# CH32L103G8R6-R0.net
KiCad netlist of a schematic drawn in Altium Designer
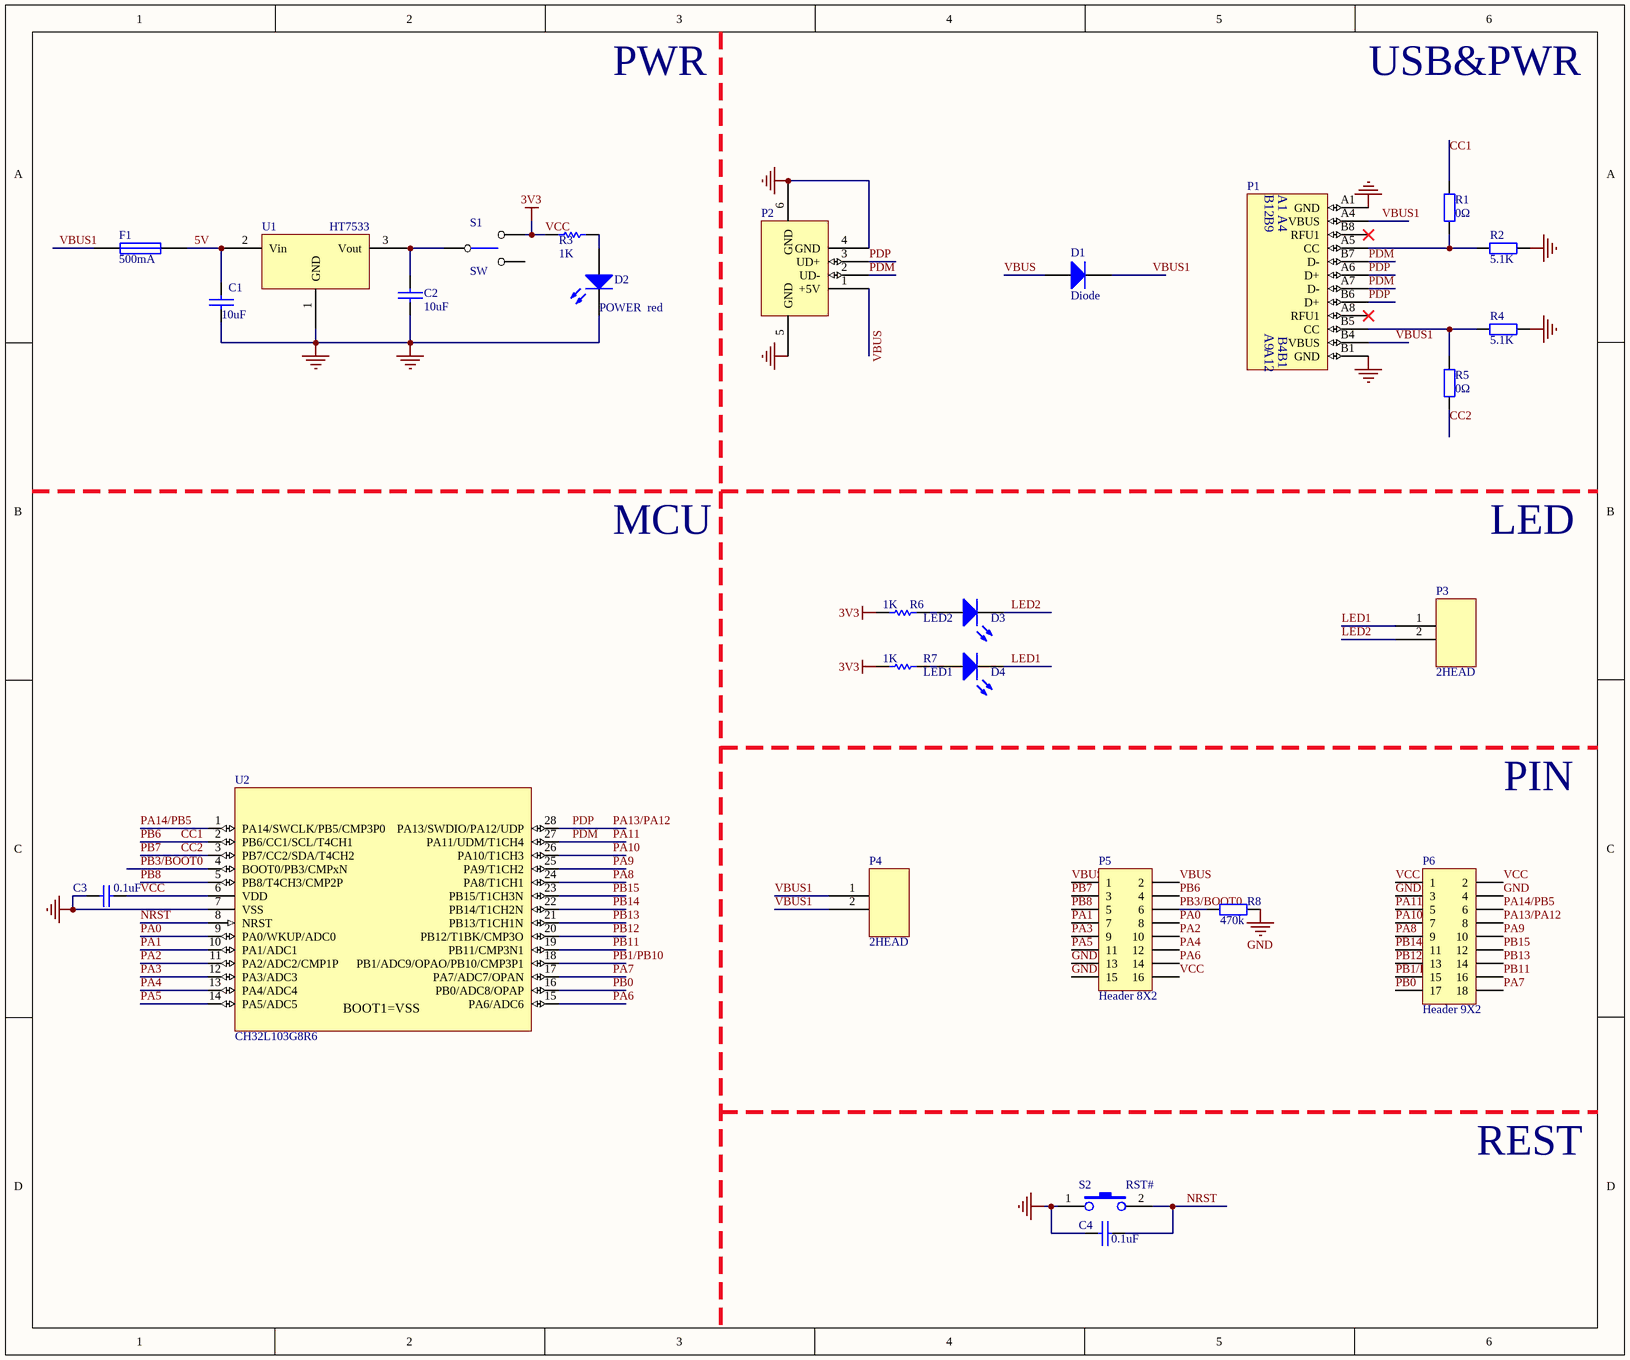
[diagram p0: CH32L103G8R6-R0.SchDoc]

(export (version "E")
  (design (tool "Eeschema 10.0.6"))
  (components
    (comp (ref "C1")
      (value "10uF")
      (footprint "0603_C")
      (description "Capacitor")
      (libsource (lib "*") (part "CAP"))
    )
    (comp (ref "C2")
      (value "10uF")
      (footprint "0603_C")
      (description "Capacitor")
      (libsource (lib "*") (part "CAP"))
    )
    (comp (ref "C3")
      (value "0.1uF")
      (footprint "0603_C")
      (description "Capacitor")
      (fields (field (name "PUBLISHER") "Altium Limited"))
      (libsource (lib "*") (part "Cap"))
    )
    (comp (ref "C4")
      (value "0.1uF")
      (footprint "0603_C")
      (description "Capacitor")
      (libsource (lib "") (part "CAP_1"))
    )
    (comp (ref "D1")
      (value "Diode")
      (footprint "SOD-123")
      (description "Default Diode")
      (fields (field (name "PUBLISHER") "Altium Limited"))
      (libsource (lib "Miscellaneous Devices") (part "Diode"))
    )
    (comp (ref "D2")
      (value "POWER  red")
      (footprint "0603+")
      (description "Typical INFRARED GaAs LED")
      (fields (field (name "PUBLISHER") "Altium Limited"))
      (libsource (lib "*") (part "LED0"))
    )
    (comp (ref "D3")
      (value "LED2")
      (footprint "0603+")
      (description "Typical INFRARED GaAs LED")
      (fields (field (name "PUBLISHER") "Altium Limited"))
      (libsource (lib "*") (part "LED0"))
    )
    (comp (ref "D4")
      (value "LED1")
      (footprint "0603+")
      (description "Typical INFRARED GaAs LED")
      (fields (field (name "PUBLISHER") "Altium Limited"))
      (libsource (lib "*") (part "LED0"))
    )
    (comp (ref "F1")
      (value "500mA")
      (footprint "0603")
      (description "Fuse")
      (libsource (lib "*") (part "FUSE1"))
    )
    (comp (ref "P1")
      (value "TYPE-C")
      (footprint "TYPE-C-Receptacle-2.0")
      (libsource (lib "*") (part "TYPE-C1"))
    )
    (comp (ref "P2")
      (value "USB_A")
      (footprint "USBAF")
      (description "USB Port")
      (libsource (lib "*") (part "USB"))
    )
    (comp (ref "P3") (value "2HEAD") (footprint "SIP2-2.54mm") (libsource (lib "*") (part "2HEAD")))
    (comp (ref "P4") (value "2HEAD") (footprint "SIP2-2.54mm") (libsource (lib "*") (part "2HEAD")))
    (comp (ref "P5")
      (value "Header 8X2")
      (footprint "HDR2X8")
      (description "Header, 8-Pin, Dual row")
      (fields (field (name "PUBLISHER") "Altium Limited"))
      (libsource (lib "Miscellaneous Connectors") (part "Header 8X2"))
    )
    (comp (ref "P6")
      (value "Header 9X2")
      (footprint "HDR2X9")
      (description "Header, 9-Pin, Dual row")
      (fields (field (name "PUBLISHER") "Altium Limited"))
      (libsource (lib "Miscellaneous Connectors") (part "Header 9X2"))
    )
    (comp (ref "R1")
      (value "0Ω")
      (footprint "0603")
      (description "Resistor")
      (libsource (lib "") (part "Res2_1"))
    )
    (comp (ref "R2")
      (value "5.1K")
      (footprint "0603")
      (description "Resistor")
      (libsource (lib "Miscellaneous Devices") (part "Res2"))
    )
    (comp (ref "R3")
      (value "1K")
      (footprint "0603")
      (description "Semiconductor Resistor")
      (libsource (lib "*") (part "Res Semi"))
    )
    (comp (ref "R4")
      (value "5.1K")
      (footprint "0603")
      (description "Resistor")
      (libsource (lib "Miscellaneous Devices") (part "Res2"))
    )
    (comp (ref "R5")
      (value "0Ω")
      (footprint "0603")
      (description "Resistor")
      (libsource (lib "") (part "Res2_1"))
    )
    (comp (ref "R6")
      (value "1K")
      (footprint "0603")
      (description "Semiconductor Resistor")
      (libsource (lib "*") (part "Res Semi"))
    )
    (comp (ref "R7")
      (value "1K")
      (footprint "0603")
      (description "Semiconductor Resistor")
      (libsource (lib "*") (part "Res Semi"))
    )
    (comp (ref "R8")
      (value "470k")
      (footprint "0603")
      (description "Resistor")
      (libsource (lib "") (part "Res2_2"))
    )
    (comp (ref "S1") (value "SW") (footprint "SW1") (libsource (lib "*") (part "SW")))
    (comp (ref "S2")
      (value "RST#")
      (footprint "SMD_6.1x3.65x2.5mm-KEY")
      (libsource (lib "wch_sch_others") (part "KEY1"))
    )
    (comp (ref "U1")
      (value "HT7533")
      (footprint "SOT-89")
      (libsource (lib "wch_sch_others") (part "1117-3.3V"))
    )
    (comp (ref "U2")
      (value "CH32L103G8R6")
      (footprint "QSOP28")
      (description "RISC-V LMD-MCU, 96MHz, USB, Type-C, CAN, OPA, lower power")
      (libsource (lib "CHXXX") (part "CH32L103G8R6"))
    )
  )
  (nets
    (net (code "1") (name "/5V") (class "Default")
      (node (ref "C1") (pin "1") (pinfunction "1_1") (pintype "passive"))
      (node (ref "F1") (pin "2") (pinfunction "2_2") (pintype "passive"))
      (node (ref "U1") (pin "2") (pinfunction "Vin_2") (pintype "passive"))
    )
    (net (code "3") (name "/CC1") (class "Default")
      (node (ref "P5") (pin "4") (pinfunction "4_4") (pintype "passive"))
      (node (ref "R1") (pin "2") (pinfunction "2_2") (pintype "passive"))
      (node (ref "U2") (pin "2") (pinfunction "PB6/CC1/SCL/T4CH1_2") (pintype "bidirectional"))
    )
    (net (code "4") (name "/CC2") (class "Default")
      (node (ref "P5") (pin "3") (pinfunction "3_3") (pintype "passive"))
      (node (ref "R5") (pin "1") (pinfunction "1_1") (pintype "passive"))
      (node (ref "U2") (pin "3") (pinfunction "PB7/CC2/SDA/T4CH2_3") (pintype "bidirectional"))
    )
    (net (code "5") (name "/LED1") (class "Default")
      (node (ref "D4") (pin "2") (pinfunction "K_2") (pintype "passive"))
      (node (ref "P3") (pin "1") (pintype "passive"))
    )
    (net (code "6") (name "/LED2") (class "Default")
      (node (ref "D3") (pin "2") (pinfunction "K_2") (pintype "passive"))
      (node (ref "P3") (pin "2") (pintype "passive"))
    )
    (net (code "7") (name "/NRST") (class "Default")
      (node (ref "C4") (pin "2") (pinfunction "2_2") (pintype "passive"))
      (node (ref "S2") (pin "2") (pinfunction "2_2") (pintype "passive"))
      (node (ref "U2") (pin "8") (pinfunction "NRST_8") (pintype "input"))
    )
    (net (code "8") (name "/PA0") (class "Default")
      (node (ref "P5") (pin "8") (pinfunction "8_8") (pintype "passive"))
      (node (ref "U2") (pin "9") (pinfunction "PA0/WKUP/ADC0_9") (pintype "bidirectional"))
    )
    (net (code "9") (name "/PA1") (class "Default")
      (node (ref "P5") (pin "7") (pinfunction "7_7") (pintype "passive"))
      (node (ref "U2") (pin "10") (pinfunction "PA1/ADC1_10") (pintype "bidirectional"))
    )
    (net (code "10") (name "/PA2") (class "Default")
      (node (ref "P5") (pin "10") (pinfunction "10_10") (pintype "passive"))
      (node (ref "U2") (pin "11") (pinfunction "PA2/ADC2/CMP1P_11") (pintype "bidirectional"))
    )
    (net (code "11") (name "/PA3") (class "Default")
      (node (ref "P5") (pin "9") (pinfunction "9_9") (pintype "passive"))
      (node (ref "U2") (pin "12") (pinfunction "PA3/ADC3_12") (pintype "bidirectional"))
    )
    (net (code "12") (name "/PA4") (class "Default")
      (node (ref "P5") (pin "12") (pinfunction "12_12") (pintype "passive"))
      (node (ref "U2") (pin "13") (pinfunction "PA4/ADC4_13") (pintype "bidirectional"))
    )
    (net (code "13") (name "/PA5") (class "Default")
      (node (ref "P5") (pin "11") (pinfunction "11_11") (pintype "passive"))
      (node (ref "U2") (pin "14") (pinfunction "PA5/ADC5_14") (pintype "bidirectional"))
    )
    (net (code "14") (name "/PA6") (class "Default")
      (node (ref "P5") (pin "14") (pinfunction "14_14") (pintype "passive"))
      (node (ref "U2") (pin "15") (pinfunction "PA6/ADC6_15") (pintype "bidirectional"))
    )
    (net (code "15") (name "/PA7") (class "Default")
      (node (ref "P6") (pin "18") (pinfunction "18_18") (pintype "passive"))
      (node (ref "U2") (pin "17") (pinfunction "PA7/ADC7/OPAN_17") (pintype "bidirectional"))
    )
    (net (code "16") (name "/PA8") (class "Default")
      (node (ref "P6") (pin "9") (pinfunction "9_9") (pintype "passive"))
      (node (ref "U2") (pin "24") (pinfunction "PA8/T1CH1_24") (pintype "bidirectional"))
    )
    (net (code "17") (name "/PA9") (class "Default")
      (node (ref "P6") (pin "10") (pinfunction "10_10") (pintype "passive"))
      (node (ref "U2") (pin "25") (pinfunction "PA9/T1CH2_25") (pintype "bidirectional"))
    )
    (net (code "18") (name "/PA10") (class "Default")
      (node (ref "P6") (pin "7") (pinfunction "7_7") (pintype "passive"))
      (node (ref "U2") (pin "26") (pinfunction "PA10/T1CH3_26") (pintype "bidirectional"))
    )
    (net (code "19") (name "/PA11") (class "Default")
      (node (ref "P1") (pin "A7") (pinfunction "D-_A7") (pintype "bidirectional"))
      (node (ref "P1") (pin "B7") (pinfunction "D-_B7") (pintype "bidirectional"))
      (node (ref "P2") (pin "2") (pinfunction "UD-_2") (pintype "bidirectional"))
      (node (ref "P6") (pin "5") (pinfunction "5_5") (pintype "passive"))
      (node (ref "U2") (pin "27") (pinfunction "PA11/UDM/T1CH4_27") (pintype "bidirectional"))
    )
    (net (code "20") (name "/PA13{slash}PA12") (class "Default")
      (node (ref "P1") (pin "A6") (pinfunction "D+_A6") (pintype "bidirectional"))
      (node (ref "P1") (pin "B6") (pinfunction "D+_B6") (pintype "bidirectional"))
      (node (ref "P2") (pin "3") (pinfunction "UD+_3") (pintype "bidirectional"))
      (node (ref "P6") (pin "8") (pinfunction "8_8") (pintype "passive"))
      (node (ref "U2") (pin "28") (pinfunction "PA13/SWDIO/PA12/UDP_28") (pintype "bidirectional"))
    )
    (net (code "21") (name "/PA14{slash}PB5") (class "Default")
      (node (ref "P6") (pin "6") (pinfunction "6_6") (pintype "passive"))
      (node (ref "U2") (pin "1") (pinfunction "PA14/SWCLK/PB5/CMP3P0_1") (pintype "bidirectional"))
    )
    (net (code "22") (name "/PB0") (class "Default")
      (node (ref "P6") (pin "17") (pinfunction "17_17") (pintype "passive"))
      (node (ref "U2") (pin "16") (pinfunction "PB0/ADC8/OPAP_16") (pintype "bidirectional"))
    )
    (net (code "23") (name "/PB1{slash}PB10") (class "Default")
      (node (ref "P6") (pin "15") (pinfunction "15_15") (pintype "passive"))
      (node (ref "U2") (pin "18") (pinfunction "PB1/ADC9/OPAO/PB10/CMP3P1_18") (pintype "bidirectional"))
    )
    (net (code "24") (name "/PB3{slash}BOOT0") (class "Default")
      (node (ref "P5") (pin "6") (pinfunction "6_6") (pintype "passive"))
      (node (ref "R8") (pin "2") (pinfunction "2_2") (pintype "passive"))
      (node (ref "U2") (pin "4") (pinfunction "BOOT0/PB3/CMPxN_4") (pintype "bidirectional"))
    )
    (net (code "25") (name "/PB8") (class "Default")
      (node (ref "P5") (pin "5") (pinfunction "5_5") (pintype "passive"))
      (node (ref "U2") (pin "5") (pinfunction "PB8/T4CH3/CMP2P_5") (pintype "bidirectional"))
    )
    (net (code "26") (name "/PB11") (class "Default")
      (node (ref "P6") (pin "16") (pinfunction "16_16") (pintype "passive"))
      (node (ref "U2") (pin "19") (pinfunction "PB11/CMP3N1_19") (pintype "bidirectional"))
    )
    (net (code "27") (name "/PB12") (class "Default")
      (node (ref "P6") (pin "13") (pinfunction "13_13") (pintype "passive"))
      (node (ref "U2") (pin "20") (pinfunction "PB12/T1BK/CMP3O_20") (pintype "bidirectional"))
    )
    (net (code "28") (name "/PB13") (class "Default")
      (node (ref "P6") (pin "14") (pinfunction "14_14") (pintype "passive"))
      (node (ref "U2") (pin "21") (pinfunction "PB13/T1CH1N_21") (pintype "bidirectional"))
    )
    (net (code "29") (name "/PB14") (class "Default")
      (node (ref "P6") (pin "11") (pinfunction "11_11") (pintype "passive"))
      (node (ref "U2") (pin "22") (pinfunction "PB14/T1CH2N_22") (pintype "bidirectional"))
    )
    (net (code "30") (name "/PB15") (class "Default")
      (node (ref "P6") (pin "12") (pinfunction "12_12") (pintype "passive"))
      (node (ref "U2") (pin "23") (pinfunction "PB15/T1CH3N_23") (pintype "bidirectional"))
    )
    (net (code "31") (name "/VBUS") (class "Default")
      (node (ref "D1") (pin "1") (pinfunction "A_1") (pintype "passive"))
      (node (ref "P2") (pin "1") (pinfunction "+5V_1") (pintype "power_in"))
      (node (ref "P5") (pin "1") (pinfunction "1_1") (pintype "passive"))
      (node (ref "P5") (pin "2") (pinfunction "2_2") (pintype "passive"))
    )
    (net (code "32") (name "/VBUS1") (class "Default")
      (node (ref "D1") (pin "2") (pinfunction "K_2") (pintype "passive"))
      (node (ref "F1") (pin "1") (pinfunction "1_1") (pintype "passive"))
      (node (ref "P1") (pin "A4") (pinfunction "VBUS_A4") (pintype "bidirectional"))
      (node (ref "P1") (pin "B4") (pinfunction "VBUS_B4") (pintype "bidirectional"))
      (node (ref "P4") (pin "1") (pintype "passive"))
      (node (ref "P4") (pin "2") (pintype "passive"))
    )
    (net (code "33") (name "3V3") (class "Default")
      (node (ref "C3") (pin "1") (pinfunction "1_1") (pintype "passive"))
      (node (ref "P5") (pin "16") (pinfunction "16_16") (pintype "passive"))
      (node (ref "P6") (pin "1") (pinfunction "1_1") (pintype "passive"))
      (node (ref "P6") (pin "2") (pinfunction "2_2") (pintype "passive"))
      (node (ref "R3") (pin "2") (pinfunction "2_2") (pintype "passive"))
      (node (ref "R6") (pin "1") (pinfunction "1_1") (pintype "passive"))
      (node (ref "R7") (pin "1") (pinfunction "1_1") (pintype "passive"))
      (node (ref "S1") (pin "3") (pinfunction "3_3") (pintype "passive"))
      (node (ref "U2") (pin "6") (pinfunction "VDD_6") (pintype "power_in"))
    )
    (net (code "34") (name "GND") (class "Default")
      (node (ref "C1") (pin "2") (pinfunction "2_2") (pintype "passive"))
      (node (ref "C2") (pin "2") (pinfunction "2_2") (pintype "passive"))
      (node (ref "C3") (pin "2") (pinfunction "2_2") (pintype "passive"))
      (node (ref "C4") (pin "1") (pinfunction "1_1") (pintype "passive"))
      (node (ref "D2") (pin "2") (pinfunction "K_2") (pintype "passive"))
      (node (ref "P1") (pin "A1") (pinfunction "GND_A1") (pintype "bidirectional"))
      (node (ref "P1") (pin "B1") (pinfunction "GND_B1") (pintype "bidirectional"))
      (node (ref "P2") (pin "4") (pinfunction "GND_4") (pintype "power_in"))
      (node (ref "P2") (pin "5") (pinfunction "GND_5") (pintype "power_in"))
      (node (ref "P2") (pin "6") (pinfunction "GND_6") (pintype "power_in"))
      (node (ref "P5") (pin "13") (pinfunction "13_13") (pintype "passive"))
      (node (ref "P5") (pin "15") (pinfunction "15_15") (pintype "passive"))
      (node (ref "P6") (pin "3") (pinfunction "3_3") (pintype "passive"))
      (node (ref "P6") (pin "4") (pinfunction "4_4") (pintype "passive"))
      (node (ref "R2") (pin "2") (pinfunction "2_2") (pintype "passive"))
      (node (ref "R4") (pin "2") (pinfunction "2_2") (pintype "passive"))
      (node (ref "R8") (pin "1") (pinfunction "1_1") (pintype "passive"))
      (node (ref "S2") (pin "1") (pinfunction "1_1") (pintype "passive"))
      (node (ref "U1") (pin "1") (pinfunction "GND_1") (pintype "passive"))
      (node (ref "U2") (pin "7") (pinfunction "VSS_7") (pintype "power_in"))
    )
    (net (code "35") (name "Net-(D2-A)") (class "Default")
      (node (ref "D2") (pin "1") (pinfunction "A_1") (pintype "passive"))
      (node (ref "R3") (pin "1") (pinfunction "1_1") (pintype "passive"))
    )
    (net (code "36") (name "Net-(D3-A)") (class "Default")
      (node (ref "D3") (pin "1") (pinfunction "A_1") (pintype "passive"))
      (node (ref "R6") (pin "2") (pinfunction "2_2") (pintype "passive"))
    )
    (net (code "37") (name "Net-(D4-A)") (class "Default")
      (node (ref "D4") (pin "1") (pinfunction "A_1") (pintype "passive"))
      (node (ref "R7") (pin "2") (pinfunction "2_2") (pintype "passive"))
    )
    (net (code "38") (name "Net-(P1-CC-PadA5)") (class "Default")
      (node (ref "P1") (pin "A5") (pinfunction "CC_A5") (pintype "bidirectional"))
      (node (ref "R1") (pin "1") (pinfunction "1_1") (pintype "passive"))
      (node (ref "R2") (pin "1") (pinfunction "1_1") (pintype "passive"))
    )
    (net (code "39") (name "Net-(P1-CC-PadB5)") (class "Default")
      (node (ref "P1") (pin "B5") (pinfunction "CC_B5") (pintype "bidirectional"))
      (node (ref "R4") (pin "1") (pinfunction "1_1") (pintype "passive"))
      (node (ref "R5") (pin "2") (pinfunction "2_2") (pintype "passive"))
    )
    (net (code "40") (name "Net-(U1-Vout)") (class "Default")
      (node (ref "C2") (pin "1") (pinfunction "1_1") (pintype "passive"))
      (node (ref "S1") (pin "1") (pinfunction "1_1") (pintype "passive"))
      (node (ref "U1") (pin "3") (pinfunction "Vout_3") (pintype "passive"))
    )
    (net (code "41") (name "unconnected-(P1-RFU1-PadA8)") (class "Default")
      (node (ref "P1") (pin "A8") (pinfunction "RFU1_A8") (pintype "bidirectional+no_connect"))
    )
    (net (code "42") (name "unconnected-(P1-RFU1-PadB8)") (class "Default")
      (node (ref "P1") (pin "B8") (pinfunction "RFU1_B8") (pintype "bidirectional+no_connect"))
    )
    (net (code "43") (name "unconnected-(S1-Pad2)") (class "Default")
      (node (ref "S1") (pin "2") (pinfunction "2_2") (pintype "passive"))
    )
  )
)
